# MainPCB.net
KiCad netlist of a schematic drawn in Altium Designer
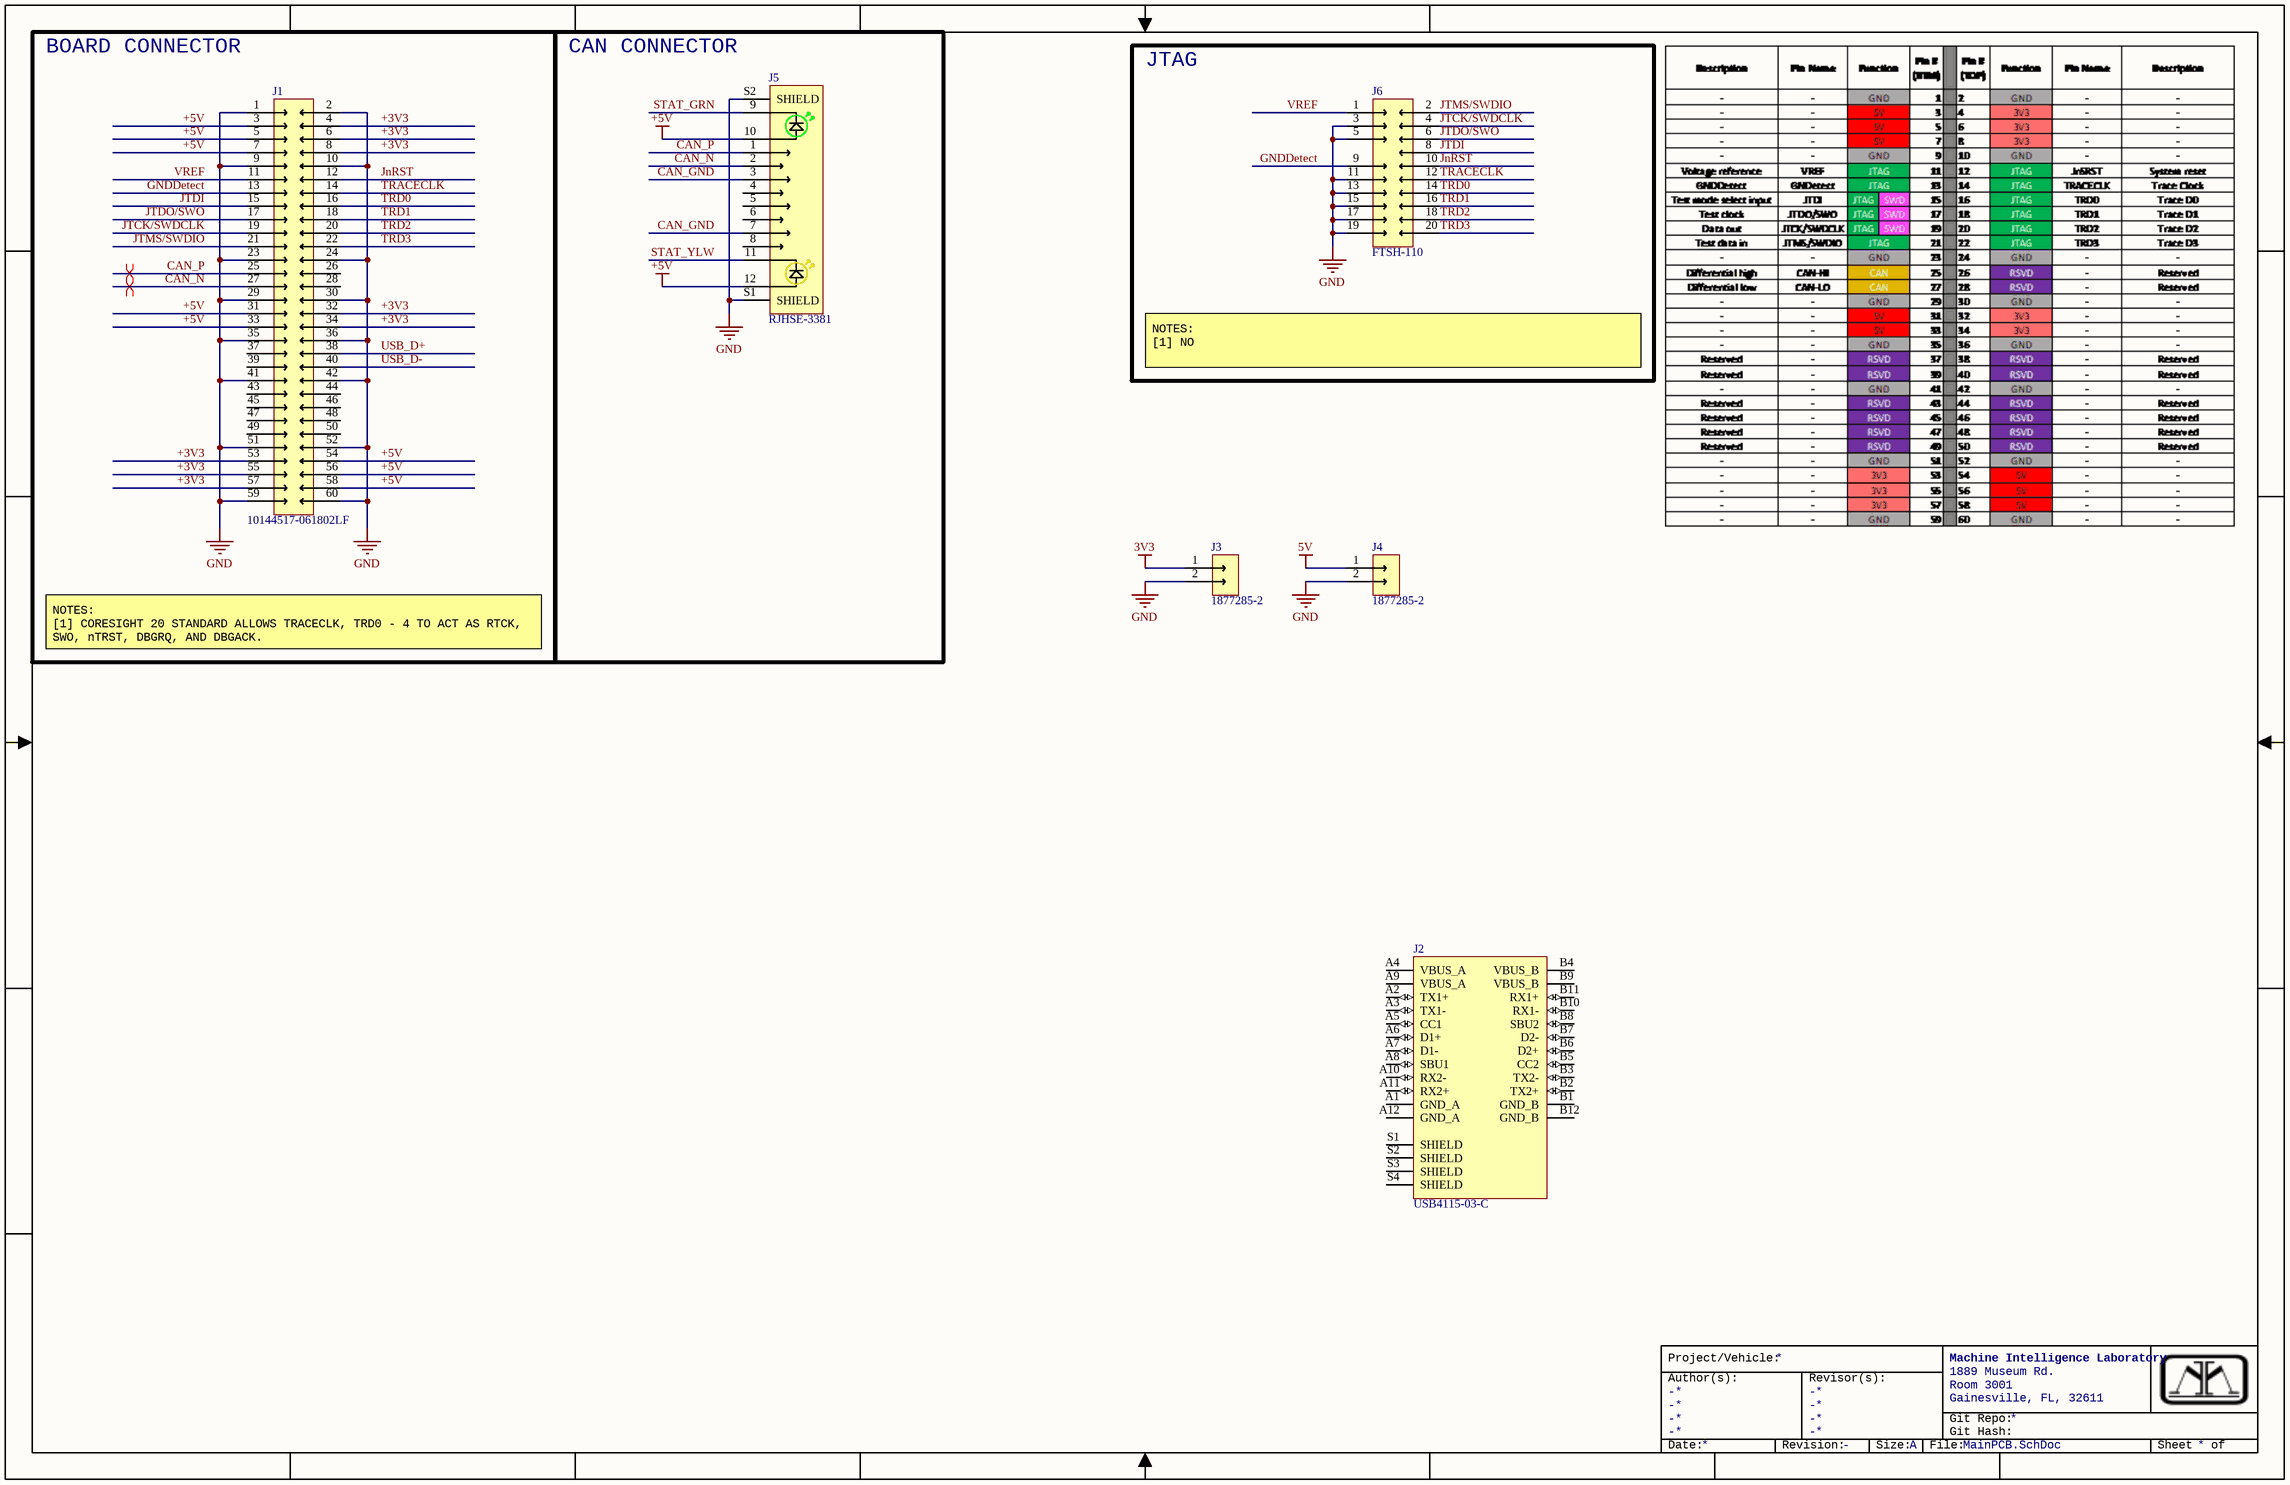
[diagram p0: MainPCB.SchDoc]

(export (version "E")
  (design (tool "Eeschema 10.0.6"))
  (components
    (comp (ref "J1")
      (value "10144517-061802LF")
      (footprint "AMPHENOL_10144517-061802LF")
      (description "CONN RCPT 60POS SMD GOLD")
      (libsource (lib "TGIS_Connectors") (part "10144517-061802LF"))
    )
    (comp (ref "J2")
      (value "USB4115-03-C")
      (footprint "GCT_USB4115-03-C_REVB2")
      (libsource (lib "TGIS_Connectors") (part "USB4115-03-C"))
    )
    (comp (ref "J3")
      (value "1877285-2")
      (footprint "TE_1877285-2")
      (libsource (lib "TGIS_Connectors") (part "1877285-2"))
    )
    (comp (ref "J4")
      (value "1877285-2")
      (footprint "TE_1877285-2")
      (libsource (lib "TGIS_Connectors") (part "1877285-2"))
    )
    (comp (ref "J5")
      (value "RJHSE-3381")
      (footprint "AMPHENOL_RJHSE3381")
      (description "Jack Modular Connector 8p8c (RJ45, Ethernet) Vertical Shielded")
      (libsource (lib "TGIS_Connectors") (part "RJHSE-3381"))
    )
    (comp (ref "J6")
      (value "FTSH-110")
      (footprint "SAMTEC_FTSH-110-01-L-DV-007")
      (description "Connector Header Surface Mount 20 position 0.050\" (1.27mm)")
      (libsource (lib "TGIS_Connectors") (part "FTSH-110-01-L-DV-007-K"))
    )
  )
  (nets
    (net (code "1") (name "+5V") (class "Default")
      (node (ref "J1") (pin "3") (pinfunction "3_3") (pintype "passive"))
      (node (ref "J1") (pin "31") (pinfunction "31_31") (pintype "passive"))
      (node (ref "J1") (pin "33") (pinfunction "33_33") (pintype "passive"))
      (node (ref "J1") (pin "5") (pinfunction "5_5") (pintype "passive"))
      (node (ref "J1") (pin "54") (pinfunction "54_54") (pintype "passive"))
      (node (ref "J1") (pin "56") (pinfunction "56_56") (pintype "passive"))
      (node (ref "J1") (pin "58") (pinfunction "58_58") (pintype "passive"))
      (node (ref "J1") (pin "7") (pinfunction "7_7") (pintype "passive"))
      (node (ref "J5") (pin "10") (pinfunction "G+_10") (pintype "passive"))
      (node (ref "J5") (pin "12") (pinfunction "Y+_12") (pintype "passive"))
    )
    (net (code "2") (name "/+3V3") (class "Default")
      (node (ref "J1") (pin "32") (pinfunction "32_32") (pintype "passive"))
      (node (ref "J1") (pin "34") (pinfunction "34_34") (pintype "passive"))
      (node (ref "J1") (pin "4") (pinfunction "4_4") (pintype "passive"))
      (node (ref "J1") (pin "53") (pinfunction "53_53") (pintype "passive"))
      (node (ref "J1") (pin "55") (pinfunction "55_55") (pintype "passive"))
      (node (ref "J1") (pin "57") (pinfunction "57_57") (pintype "passive"))
      (node (ref "J1") (pin "6") (pinfunction "6_6") (pintype "passive"))
      (node (ref "J1") (pin "8") (pinfunction "8_8") (pintype "passive"))
    )
    (net (code "3") (name "/CAN_GND") (class "Default")
      (node (ref "J5") (pin "3") (pintype "passive"))
      (node (ref "J5") (pin "7") (pintype "passive"))
    )
    (net (code "4") (name "/CAN_N") (class "Default")
      (node (ref "J1") (pin "27") (pinfunction "27_27") (pintype "passive"))
      (node (ref "J5") (pin "2") (pintype "passive"))
    )
    (net (code "5") (name "/CAN_P") (class "Default")
      (node (ref "J1") (pin "25") (pinfunction "25_25") (pintype "passive"))
      (node (ref "J5") (pin "1") (pintype "passive"))
    )
    (net (code "6") (name "/GNDDetect") (class "Default")
      (node (ref "J1") (pin "13") (pinfunction "13_13") (pintype "passive"))
      (node (ref "J6") (pin "9") (pinfunction "9_9") (pintype "passive"))
    )
    (net (code "7") (name "/JTCK{slash}SWDCLK") (class "Default")
      (node (ref "J1") (pin "19") (pinfunction "19_19") (pintype "passive"))
      (node (ref "J6") (pin "4") (pinfunction "4_4") (pintype "passive"))
    )
    (net (code "8") (name "/JTDI") (class "Default")
      (node (ref "J1") (pin "15") (pinfunction "15_15") (pintype "passive"))
      (node (ref "J6") (pin "8") (pinfunction "8_8") (pintype "passive"))
    )
    (net (code "9") (name "/JTDO{slash}SWO") (class "Default")
      (node (ref "J1") (pin "17") (pinfunction "17_17") (pintype "passive"))
      (node (ref "J6") (pin "6") (pinfunction "6_6") (pintype "passive"))
    )
    (net (code "10") (name "/JTMS{slash}SWDIO") (class "Default")
      (node (ref "J1") (pin "21") (pinfunction "21_21") (pintype "passive"))
      (node (ref "J6") (pin "2") (pinfunction "2_2") (pintype "passive"))
    )
    (net (code "11") (name "/JnRST") (class "Default")
      (node (ref "J1") (pin "12") (pinfunction "12_12") (pintype "passive"))
      (node (ref "J6") (pin "10") (pinfunction "10_10") (pintype "passive"))
    )
    (net (code "12") (name "/STAT_GRN") (class "Default")
      (node (ref "J5") (pin "9") (pinfunction "G-_9") (pintype "passive"))
    )
    (net (code "13") (name "/STAT_YLW") (class "Default")
      (node (ref "J5") (pin "11") (pinfunction "Y-_11") (pintype "passive"))
    )
    (net (code "14") (name "/TRACECLK") (class "Default")
      (node (ref "J1") (pin "14") (pinfunction "14_14") (pintype "passive"))
      (node (ref "J6") (pin "12") (pinfunction "12_12") (pintype "passive"))
    )
    (net (code "15") (name "/TRD0") (class "Default")
      (node (ref "J1") (pin "16") (pinfunction "16_16") (pintype "passive"))
      (node (ref "J6") (pin "14") (pinfunction "14_14") (pintype "passive"))
    )
    (net (code "16") (name "/TRD1") (class "Default")
      (node (ref "J1") (pin "18") (pinfunction "18_18") (pintype "passive"))
      (node (ref "J6") (pin "16") (pinfunction "16_16") (pintype "passive"))
    )
    (net (code "17") (name "/TRD2") (class "Default")
      (node (ref "J1") (pin "20") (pinfunction "20_20") (pintype "passive"))
      (node (ref "J6") (pin "18") (pinfunction "18_18") (pintype "passive"))
    )
    (net (code "18") (name "/TRD3") (class "Default")
      (node (ref "J1") (pin "22") (pinfunction "22_22") (pintype "passive"))
      (node (ref "J6") (pin "20") (pinfunction "20_20") (pintype "passive"))
    )
    (net (code "19") (name "/USB_D+") (class "Default")
      (node (ref "J1") (pin "38") (pinfunction "38_38") (pintype "passive"))
    )
    (net (code "20") (name "/USB_D-") (class "Default")
      (node (ref "J1") (pin "40") (pinfunction "40_40") (pintype "passive"))
    )
    (net (code "21") (name "/VREF") (class "Default")
      (node (ref "J1") (pin "11") (pinfunction "11_11") (pintype "passive"))
      (node (ref "J6") (pin "1") (pinfunction "1_1") (pintype "passive"))
    )
    (net (code "22") (name "3V3") (class "Default")
      (node (ref "J3") (pin "1") (pinfunction "1_1") (pintype "passive"))
    )
    (net (code "23") (name "5V") (class "Default")
      (node (ref "J4") (pin "1") (pinfunction "1_1") (pintype "passive"))
    )
    (net (code "24") (name "GND") (class "Default")
      (node (ref "J1") (pin "1") (pinfunction "1_1") (pintype "passive"))
      (node (ref "J1") (pin "10") (pinfunction "10_10") (pintype "passive"))
      (node (ref "J1") (pin "2") (pinfunction "2_2") (pintype "passive"))
      (node (ref "J1") (pin "23") (pinfunction "23_23") (pintype "passive"))
      (node (ref "J1") (pin "24") (pinfunction "24_24") (pintype "passive"))
      (node (ref "J1") (pin "29") (pinfunction "29_29") (pintype "passive"))
      (node (ref "J1") (pin "30") (pinfunction "30_30") (pintype "passive"))
      (node (ref "J1") (pin "35") (pinfunction "35_35") (pintype "passive"))
      (node (ref "J1") (pin "36") (pinfunction "36_36") (pintype "passive"))
      (node (ref "J1") (pin "41") (pinfunction "41_41") (pintype "passive"))
      (node (ref "J1") (pin "42") (pinfunction "42_42") (pintype "passive"))
      (node (ref "J1") (pin "51") (pinfunction "51_51") (pintype "passive"))
      (node (ref "J1") (pin "52") (pinfunction "52_52") (pintype "passive"))
      (node (ref "J1") (pin "59") (pinfunction "59_59") (pintype "passive"))
      (node (ref "J1") (pin "60") (pinfunction "60_60") (pintype "passive"))
      (node (ref "J1") (pin "9") (pinfunction "9_9") (pintype "passive"))
      (node (ref "J3") (pin "2") (pinfunction "2_2") (pintype "passive"))
      (node (ref "J4") (pin "2") (pinfunction "2_2") (pintype "passive"))
      (node (ref "J5") (pin "S1") (pinfunction "SHIELD_S1") (pintype "passive"))
      (node (ref "J5") (pin "S2") (pinfunction "SHIELD_S2") (pintype "passive"))
      (node (ref "J6") (pin "11") (pinfunction "11_11") (pintype "passive"))
      (node (ref "J6") (pin "13") (pinfunction "13_13") (pintype "passive"))
      (node (ref "J6") (pin "15") (pinfunction "15_15") (pintype "passive"))
      (node (ref "J6") (pin "17") (pinfunction "17_17") (pintype "passive"))
      (node (ref "J6") (pin "19") (pinfunction "19_19") (pintype "passive"))
      (node (ref "J6") (pin "3") (pinfunction "3_3") (pintype "passive"))
      (node (ref "J6") (pin "5") (pinfunction "5_5") (pintype "passive"))
    )
    (net (code "25") (name "unconnected-(J1-Pad26)") (class "Default")
      (node (ref "J1") (pin "26") (pinfunction "26_26") (pintype "passive"))
    )
    (net (code "26") (name "unconnected-(J1-Pad28)") (class "Default")
      (node (ref "J1") (pin "28") (pinfunction "28_28") (pintype "passive"))
    )
    (net (code "27") (name "unconnected-(J1-Pad37)") (class "Default")
      (node (ref "J1") (pin "37") (pinfunction "37_37") (pintype "passive"))
    )
    (net (code "28") (name "unconnected-(J1-Pad39)") (class "Default")
      (node (ref "J1") (pin "39") (pinfunction "39_39") (pintype "passive"))
    )
    (net (code "29") (name "unconnected-(J1-Pad43)") (class "Default")
      (node (ref "J1") (pin "43") (pinfunction "43_43") (pintype "passive"))
    )
    (net (code "30") (name "unconnected-(J1-Pad44)") (class "Default")
      (node (ref "J1") (pin "44") (pinfunction "44_44") (pintype "passive"))
    )
    (net (code "31") (name "unconnected-(J1-Pad45)") (class "Default")
      (node (ref "J1") (pin "45") (pinfunction "45_45") (pintype "passive"))
    )
    (net (code "32") (name "unconnected-(J1-Pad46)") (class "Default")
      (node (ref "J1") (pin "46") (pinfunction "46_46") (pintype "passive"))
    )
    (net (code "33") (name "unconnected-(J1-Pad47)") (class "Default")
      (node (ref "J1") (pin "47") (pinfunction "47_47") (pintype "passive"))
    )
    (net (code "34") (name "unconnected-(J1-Pad48)") (class "Default")
      (node (ref "J1") (pin "48") (pinfunction "48_48") (pintype "passive"))
    )
    (net (code "35") (name "unconnected-(J1-Pad49)") (class "Default")
      (node (ref "J1") (pin "49") (pinfunction "49_49") (pintype "passive"))
    )
    (net (code "36") (name "unconnected-(J1-Pad50)") (class "Default")
      (node (ref "J1") (pin "50") (pinfunction "50_50") (pintype "passive"))
    )
    (net (code "37") (name "unconnected-(J2-CC1-PadA5)") (class "Default")
      (node (ref "J2") (pin "A5") (pinfunction "CC1_A5") (pintype "bidirectional"))
    )
    (net (code "38") (name "unconnected-(J2-CC2-PadB5)") (class "Default")
      (node (ref "J2") (pin "B5") (pinfunction "CC2_B5") (pintype "bidirectional"))
    )
    (net (code "39") (name "unconnected-(J2-D1+-PadA6)") (class "Default")
      (node (ref "J2") (pin "A6") (pinfunction "D1+_A6") (pintype "bidirectional"))
    )
    (net (code "40") (name "unconnected-(J2-D1--PadA7)") (class "Default")
      (node (ref "J2") (pin "A7") (pinfunction "D1-_A7") (pintype "bidirectional"))
    )
    (net (code "41") (name "unconnected-(J2-D2+-PadB6)") (class "Default")
      (node (ref "J2") (pin "B6") (pinfunction "D2+_B6") (pintype "bidirectional"))
    )
    (net (code "42") (name "unconnected-(J2-D2--PadB7)") (class "Default")
      (node (ref "J2") (pin "B7") (pinfunction "D2-_B7") (pintype "bidirectional"))
    )
    (net (code "43") (name "unconnected-(J2-GND_A-PadA1)") (class "Default")
      (node (ref "J2") (pin "A1") (pinfunction "GND_A_A1") (pintype "power_in"))
    )
    (net (code "44") (name "unconnected-(J2-GND_A-PadA12)") (class "Default")
      (node (ref "J2") (pin "A12") (pinfunction "GND_A_A12") (pintype "power_in"))
    )
    (net (code "45") (name "unconnected-(J2-GND_B-PadB1)") (class "Default")
      (node (ref "J2") (pin "B1") (pinfunction "GND_B_B1") (pintype "power_in"))
    )
    (net (code "46") (name "unconnected-(J2-GND_B-PadB12)") (class "Default")
      (node (ref "J2") (pin "B12") (pinfunction "GND_B_B12") (pintype "power_in"))
    )
    (net (code "47") (name "unconnected-(J2-RX1+-PadB11)") (class "Default")
      (node (ref "J2") (pin "B11") (pinfunction "RX1+_B11") (pintype "bidirectional"))
    )
    (net (code "48") (name "unconnected-(J2-RX1--PadB10)") (class "Default")
      (node (ref "J2") (pin "B10") (pinfunction "RX1-_B10") (pintype "bidirectional"))
    )
    (net (code "49") (name "unconnected-(J2-RX2+-PadA11)") (class "Default")
      (node (ref "J2") (pin "A11") (pinfunction "RX2+_A11") (pintype "bidirectional"))
    )
    (net (code "50") (name "unconnected-(J2-RX2--PadA10)") (class "Default")
      (node (ref "J2") (pin "A10") (pinfunction "RX2-_A10") (pintype "bidirectional"))
    )
    (net (code "51") (name "unconnected-(J2-SBU1-PadA8)") (class "Default")
      (node (ref "J2") (pin "A8") (pinfunction "SBU1_A8") (pintype "bidirectional"))
    )
    (net (code "52") (name "unconnected-(J2-SBU2-PadB8)") (class "Default")
      (node (ref "J2") (pin "B8") (pinfunction "SBU2_B8") (pintype "bidirectional"))
    )
    (net (code "53") (name "unconnected-(J2-SHIELD-PadS1)") (class "Default")
      (node (ref "J2") (pin "S1") (pinfunction "SHIELD_S1") (pintype "passive"))
    )
    (net (code "54") (name "unconnected-(J2-SHIELD-PadS2)") (class "Default")
      (node (ref "J2") (pin "S2") (pinfunction "SHIELD_S2") (pintype "passive"))
    )
    (net (code "55") (name "unconnected-(J2-SHIELD-PadS3)") (class "Default")
      (node (ref "J2") (pin "S3") (pinfunction "SHIELD_S3") (pintype "passive"))
    )
    (net (code "56") (name "unconnected-(J2-SHIELD-PadS4)") (class "Default")
      (node (ref "J2") (pin "S4") (pinfunction "SHIELD_S4") (pintype "passive"))
    )
    (net (code "57") (name "unconnected-(J2-TX1+-PadA2)") (class "Default")
      (node (ref "J2") (pin "A2") (pinfunction "TX1+_A2") (pintype "bidirectional"))
    )
    (net (code "58") (name "unconnected-(J2-TX1--PadA3)") (class "Default")
      (node (ref "J2") (pin "A3") (pinfunction "TX1-_A3") (pintype "bidirectional"))
    )
    (net (code "59") (name "unconnected-(J2-TX2+-PadB2)") (class "Default")
      (node (ref "J2") (pin "B2") (pinfunction "TX2+_B2") (pintype "bidirectional"))
    )
    (net (code "60") (name "unconnected-(J2-TX2--PadB3)") (class "Default")
      (node (ref "J2") (pin "B3") (pinfunction "TX2-_B3") (pintype "bidirectional"))
    )
    (net (code "61") (name "unconnected-(J2-VBUS_A-PadA4)") (class "Default")
      (node (ref "J2") (pin "A4") (pinfunction "VBUS_A_A4") (pintype "power_in"))
    )
    (net (code "62") (name "unconnected-(J2-VBUS_A-PadA9)") (class "Default")
      (node (ref "J2") (pin "A9") (pinfunction "VBUS_A_A9") (pintype "power_in"))
    )
    (net (code "63") (name "unconnected-(J2-VBUS_B-PadB4)") (class "Default")
      (node (ref "J2") (pin "B4") (pinfunction "VBUS_B_B4") (pintype "power_in"))
    )
    (net (code "64") (name "unconnected-(J2-VBUS_B-PadB9)") (class "Default")
      (node (ref "J2") (pin "B9") (pinfunction "VBUS_B_B9") (pintype "power_in"))
    )
    (net (code "65") (name "unconnected-(J5-Pad4)") (class "Default")
      (node (ref "J5") (pin "4") (pintype "passive"))
    )
    (net (code "66") (name "unconnected-(J5-Pad5)") (class "Default")
      (node (ref "J5") (pin "5") (pintype "passive"))
    )
    (net (code "67") (name "unconnected-(J5-Pad6)") (class "Default")
      (node (ref "J5") (pin "6") (pintype "passive"))
    )
    (net (code "68") (name "unconnected-(J5-Pad8)") (class "Default")
      (node (ref "J5") (pin "8") (pintype "passive"))
    )
  )
)
